# converting_to_smd.net
KiCad netlist of a schematic drawn in EAGLE
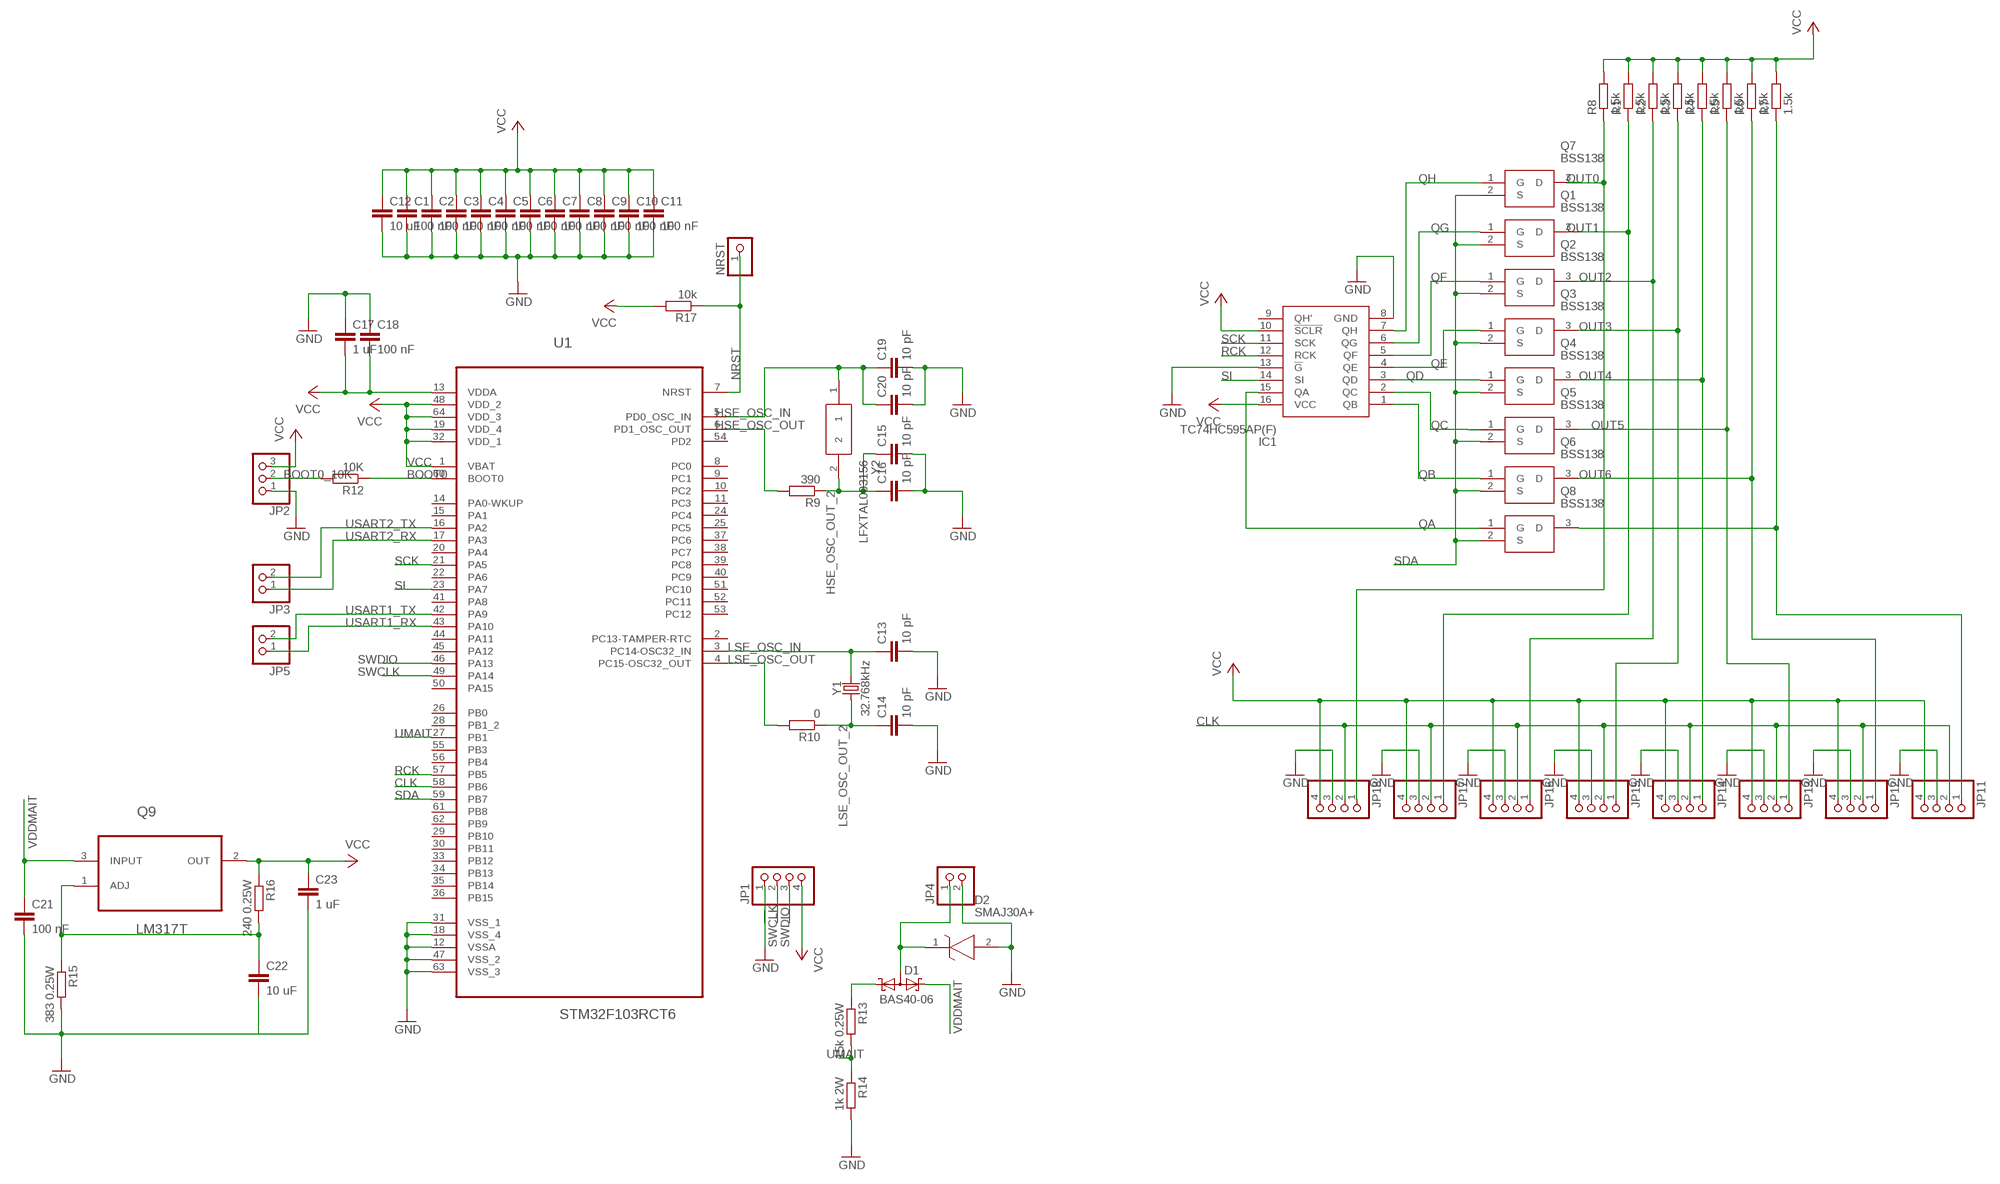
[diagram p0: schematic, sheet 1]

(export (version "E")
  (design (tool "Eeschema 10.0.6"))
  (components
    (comp (ref "C1")
      (value "100 nF")
      (footprint "eagle-import:C0603")
      (libsource (lib "eagle-import") (part "C-EUC0603"))
    )
    (comp (ref "C2")
      (value "100 nF")
      (footprint "eagle-import:C0603")
      (libsource (lib "eagle-import") (part "C-EUC0603"))
    )
    (comp (ref "C3")
      (value "100 nF")
      (footprint "eagle-import:C0603")
      (libsource (lib "eagle-import") (part "C-EUC0603"))
    )
    (comp (ref "C4")
      (value "100 nF")
      (footprint "eagle-import:C0603")
      (libsource (lib "eagle-import") (part "C-EUC0603"))
    )
    (comp (ref "C5")
      (value "100 nF")
      (footprint "eagle-import:C0603")
      (libsource (lib "eagle-import") (part "C-EUC0603"))
    )
    (comp (ref "C6")
      (value "100 nF")
      (footprint "eagle-import:C0603")
      (libsource (lib "eagle-import") (part "C-EUC0603"))
    )
    (comp (ref "C7")
      (value "100 nF")
      (footprint "eagle-import:C0603")
      (libsource (lib "eagle-import") (part "C-EUC0603"))
    )
    (comp (ref "C8")
      (value "100 nF")
      (footprint "eagle-import:C0603")
      (libsource (lib "eagle-import") (part "C-EUC0603"))
    )
    (comp (ref "C9")
      (value "100 nF")
      (footprint "eagle-import:C0603")
      (libsource (lib "eagle-import") (part "C-EUC0603"))
    )
    (comp (ref "C10")
      (value "100 nF")
      (footprint "eagle-import:C0603")
      (libsource (lib "eagle-import") (part "C-EUC0603"))
    )
    (comp (ref "C11")
      (value "100 nF")
      (footprint "eagle-import:C0603")
      (libsource (lib "eagle-import") (part "C-EUC0603"))
    )
    (comp (ref "C12")
      (value "10 uF")
      (footprint "eagle-import:C0603")
      (libsource (lib "eagle-import") (part "resistor_348_C-EUC0603"))
    )
    (comp (ref "C13")
      (value "10 pF")
      (footprint "eagle-import:C0805")
      (libsource (lib "eagle-import") (part "resistor_348_C-EUC0805"))
    )
    (comp (ref "C14")
      (value "10 pF")
      (footprint "eagle-import:C0805")
      (libsource (lib "eagle-import") (part "resistor_348_C-EUC0805"))
    )
    (comp (ref "C15")
      (value "10 pF")
      (footprint "eagle-import:C0805")
      (libsource (lib "eagle-import") (part "resistor_348_C-EUC0805"))
    )
    (comp (ref "C16")
      (value "10 pF")
      (footprint "eagle-import:C0805")
      (libsource (lib "eagle-import") (part "resistor_348_C-EUC0805"))
    )
    (comp (ref "C17")
      (value "1 uF")
      (footprint "eagle-import:C0603")
      (libsource (lib "eagle-import") (part "C-EUC0603"))
    )
    (comp (ref "C18")
      (value "100 nF")
      (footprint "eagle-import:C0603")
      (libsource (lib "eagle-import") (part "C-EUC0603"))
    )
    (comp (ref "C19")
      (value "10 pF")
      (footprint "eagle-import:C0805")
      (libsource (lib "eagle-import") (part "resistor_348_C-EUC0805"))
    )
    (comp (ref "C20")
      (value "10 pF")
      (footprint "eagle-import:C0805")
      (libsource (lib "eagle-import") (part "resistor_348_C-EUC0805"))
    )
    (comp (ref "C21")
      (value "100 nF")
      (footprint "eagle-import:C0603")
      (libsource (lib "eagle-import") (part "C-EUC0603"))
    )
    (comp (ref "C22")
      (value "10 uF")
      (footprint "eagle-import:C0603")
      (libsource (lib "eagle-import") (part "resistor_348_C-EUC0603"))
    )
    (comp (ref "C23")
      (value "1 uF")
      (footprint "eagle-import:C0603")
      (libsource (lib "eagle-import") (part "C-EUC0603"))
    )
    (comp (ref "D1")
      (value "BAS40-06")
      (footprint "eagle-import:SOT23")
      (libsource (lib "eagle-import") (part "BAS40-06"))
    )
    (comp (ref "D2")
      (value "SMAJ30A+")
      (footprint "eagle-import:DIOM5026X262N")
      (libsource (lib "eagle-import") (part "SMAJ30A+"))
    )
    (comp (ref "IC1")
      (value "TC74HC595AP(F)")
      (footprint "eagle-import:DIP762W60P254L1925H445Q16N")
      (fields (field (name "RS_PART_NUMBER") "5400095P"))
      (libsource (lib "eagle-import") (part "TC74HC595AP(F)"))
    )
    (comp (ref "JP1")
      (value "PINHD-1X4")
      (footprint "eagle-import:1X04")
      (libsource (lib "eagle-import") (part "PINHD-1X4"))
    )
    (comp (ref "JP2")
      (value "PINHD-1X3")
      (footprint "eagle-import:1X03")
      (libsource (lib "eagle-import") (part "PINHD-1X3"))
    )
    (comp (ref "JP3")
      (value "PINHD-1X2")
      (footprint "eagle-import:1X02")
      (libsource (lib "eagle-import") (part "PINHD-1X2"))
    )
    (comp (ref "JP4")
      (value "PINHD-1X2")
      (footprint "eagle-import:1X02")
      (libsource (lib "eagle-import") (part "PINHD-1X2"))
    )
    (comp (ref "JP5")
      (value "PINHD-1X2")
      (footprint "eagle-import:1X02")
      (libsource (lib "eagle-import") (part "PINHD-1X2"))
    )
    (comp (ref "JP11")
      (value "PINHD-1X4")
      (footprint "eagle-import:1X04")
      (libsource (lib "eagle-import") (part "PINHD-1X4"))
    )
    (comp (ref "JP12")
      (value "PINHD-1X4")
      (footprint "eagle-import:1X04")
      (libsource (lib "eagle-import") (part "PINHD-1X4"))
    )
    (comp (ref "JP13")
      (value "PINHD-1X4")
      (footprint "eagle-import:1X04")
      (libsource (lib "eagle-import") (part "PINHD-1X4"))
    )
    (comp (ref "JP14")
      (value "PINHD-1X4")
      (footprint "eagle-import:1X04")
      (libsource (lib "eagle-import") (part "PINHD-1X4"))
    )
    (comp (ref "JP15")
      (value "PINHD-1X4")
      (footprint "eagle-import:1X04")
      (libsource (lib "eagle-import") (part "PINHD-1X4"))
    )
    (comp (ref "JP16")
      (value "PINHD-1X4")
      (footprint "eagle-import:1X04")
      (libsource (lib "eagle-import") (part "PINHD-1X4"))
    )
    (comp (ref "JP17")
      (value "PINHD-1X4")
      (footprint "eagle-import:1X04")
      (libsource (lib "eagle-import") (part "PINHD-1X4"))
    )
    (comp (ref "JP18")
      (value "PINHD-1X4")
      (footprint "eagle-import:1X04")
      (libsource (lib "eagle-import") (part "PINHD-1X4"))
    )
    (comp (ref "NRST")
      (value "PINHD-1X1")
      (footprint "eagle-import:1X01")
      (libsource (lib "eagle-import") (part "PINHD-1X1"))
    )
    (comp (ref "Q1")
      (value "BSS138")
      (footprint "eagle-import:SOT95P240X120-3N")
      (fields (field (name "MOUSER_PART_NUMBER") "512-BSS138") (field (name "RS_PART_NUMBER") "1241694"))
      (libsource (lib "eagle-import") (part "BSS138"))
    )
    (comp (ref "Q2")
      (value "BSS138")
      (footprint "eagle-import:SOT95P240X120-3N")
      (fields (field (name "MOUSER_PART_NUMBER") "512-BSS138") (field (name "RS_PART_NUMBER") "1241694"))
      (libsource (lib "eagle-import") (part "BSS138"))
    )
    (comp (ref "Q3")
      (value "BSS138")
      (footprint "eagle-import:SOT95P240X120-3N")
      (fields (field (name "MOUSER_PART_NUMBER") "512-BSS138") (field (name "RS_PART_NUMBER") "1241694"))
      (libsource (lib "eagle-import") (part "BSS138"))
    )
    (comp (ref "Q4")
      (value "BSS138")
      (footprint "eagle-import:SOT95P240X120-3N")
      (fields (field (name "MOUSER_PART_NUMBER") "512-BSS138") (field (name "RS_PART_NUMBER") "1241694"))
      (libsource (lib "eagle-import") (part "BSS138"))
    )
    (comp (ref "Q5")
      (value "BSS138")
      (footprint "eagle-import:SOT95P240X120-3N")
      (fields (field (name "MOUSER_PART_NUMBER") "512-BSS138") (field (name "RS_PART_NUMBER") "1241694"))
      (libsource (lib "eagle-import") (part "BSS138"))
    )
    (comp (ref "Q6")
      (value "BSS138")
      (footprint "eagle-import:SOT95P240X120-3N")
      (fields (field (name "MOUSER_PART_NUMBER") "512-BSS138") (field (name "RS_PART_NUMBER") "1241694"))
      (libsource (lib "eagle-import") (part "BSS138"))
    )
    (comp (ref "Q7")
      (value "BSS138")
      (footprint "eagle-import:SOT95P240X120-3N")
      (fields (field (name "MOUSER_PART_NUMBER") "512-BSS138") (field (name "RS_PART_NUMBER") "1241694"))
      (libsource (lib "eagle-import") (part "BSS138"))
    )
    (comp (ref "Q8")
      (value "BSS138")
      (footprint "eagle-import:SOT95P240X120-3N")
      (fields (field (name "MOUSER_PART_NUMBER") "512-BSS138") (field (name "RS_PART_NUMBER") "1241694"))
      (libsource (lib "eagle-import") (part "BSS138"))
    )
    (comp (ref "Q9")
      (value "LM317T")
      (footprint "eagle-import:TO254P450X1020X2000-3P")
      (fields (field (name "MF") "Texas Instruments"))
      (libsource (lib "eagle-import") (part "LM317T"))
    )
    (comp (ref "R1")
      (value "1.5k")
      (footprint "eagle-import:0207_15")
      (libsource (lib "eagle-import") (part "R-EU_0207/15"))
    )
    (comp (ref "R2")
      (value "1.5k")
      (footprint "eagle-import:0207_15")
      (libsource (lib "eagle-import") (part "R-EU_0207/15"))
    )
    (comp (ref "R3")
      (value "1.5k")
      (footprint "eagle-import:0207_15")
      (libsource (lib "eagle-import") (part "R-EU_0207/15"))
    )
    (comp (ref "R4")
      (value "1.5k")
      (footprint "eagle-import:0207_15")
      (libsource (lib "eagle-import") (part "R-EU_0207/15"))
    )
    (comp (ref "R5")
      (value "1.5k")
      (footprint "eagle-import:0207_15")
      (libsource (lib "eagle-import") (part "R-EU_0207/15"))
    )
    (comp (ref "R6")
      (value "1.5k")
      (footprint "eagle-import:0207_15")
      (libsource (lib "eagle-import") (part "R-EU_0207/15"))
    )
    (comp (ref "R7")
      (value "1.5k")
      (footprint "eagle-import:0207_15")
      (libsource (lib "eagle-import") (part "R-EU_0207/15"))
    )
    (comp (ref "R8")
      (value "1.5k")
      (footprint "eagle-import:0207_15")
      (libsource (lib "eagle-import") (part "R-EU_0207/15"))
    )
    (comp (ref "R9")
      (value "390")
      (footprint "eagle-import:0207_15")
      (libsource (lib "eagle-import") (part "R-EU_0207/15"))
    )
    (comp (ref "R10")
      (value "0")
      (footprint "eagle-import:0207_15")
      (libsource (lib "eagle-import") (part "R-EU_0207/15"))
    )
    (comp (ref "R12")
      (value "10K")
      (footprint "eagle-import:0207_15")
      (libsource (lib "eagle-import") (part "R-EU_0207/15"))
    )
    (comp (ref "R13")
      (value "15k 0.25W")
      (footprint "eagle-import:0207_15")
      (libsource (lib "eagle-import") (part "R-EU_0207/15"))
    )
    (comp (ref "R14")
      (value "1k 2W")
      (footprint "eagle-import:0207_15")
      (libsource (lib "eagle-import") (part "R-EU_0207/15"))
    )
    (comp (ref "R15")
      (value "383 0.25W")
      (footprint "eagle-import:0207_15")
      (libsource (lib "eagle-import") (part "R-EU_0207/15"))
    )
    (comp (ref "R16")
      (value "240 0.25W")
      (footprint "eagle-import:0207_15")
      (libsource (lib "eagle-import") (part "R-EU_0207/15"))
    )
    (comp (ref "R17")
      (value "10k")
      (footprint "eagle-import:0207_15")
      (libsource (lib "eagle-import") (part "R-EU_0207/15"))
    )
    (comp (ref "U1")
      (value "STM32F103RCT6")
      (footprint "eagle-import:QFP50P1200X1200X160-64N")
      (fields (field (name "MF") "STMicroelectronics"))
      (libsource (lib "eagle-import") (part "STM32F103RCT6"))
    )
    (comp (ref "Y1")
      (value "32.768kHz")
      (footprint "eagle-import:CRYSTAL-PTH-2X6-CYL")
      (libsource (lib "eagle-import") (part "CRYSTAL-32.768KHZPTH-2X6"))
    )
    (comp (ref "Y2")
      (value "LFXTAL003156")
      (footprint "eagle-import:IQD-HC-49-4H")
      (fields (field (name "RS_PART_NUMBER") "1533666"))
      (libsource (lib "eagle-import") (part "LFXTAL003156"))
    )
  )
  (nets
    (net (code "1") (name "/BOOT0") (class "Default")
      (node (ref "R12") (pin "1") (pinfunction "1_1") (pintype "passive"))
      (node (ref "U1") (pin "60") (pinfunction "BOOT0_60") (pintype "passive"))
    )
    (net (code "2") (name "/BOOT0_10K") (class "Default")
      (node (ref "JP2") (pin "2") (pinfunction "2_2") (pintype "passive"))
      (node (ref "R12") (pin "2") (pinfunction "2_2") (pintype "passive"))
    )
    (net (code "3") (name "/CLK") (class "Default")
      (node (ref "JP11") (pin "2") (pinfunction "2_2") (pintype "passive"))
      (node (ref "JP12") (pin "2") (pinfunction "2_2") (pintype "passive"))
      (node (ref "JP13") (pin "2") (pinfunction "2_2") (pintype "passive"))
      (node (ref "JP14") (pin "2") (pinfunction "2_2") (pintype "passive"))
      (node (ref "JP15") (pin "2") (pinfunction "2_2") (pintype "passive"))
      (node (ref "JP16") (pin "2") (pinfunction "2_2") (pintype "passive"))
      (node (ref "JP17") (pin "2") (pinfunction "2_2") (pintype "passive"))
      (node (ref "JP18") (pin "2") (pinfunction "2_2") (pintype "passive"))
      (node (ref "U1") (pin "58") (pinfunction "PB6_58") (pintype "bidirectional"))
    )
    (net (code "4") (name "/HSE_OSC_IN") (class "Default")
      (node (ref "C19") (pin "1") (pinfunction "1_1") (pintype "passive"))
      (node (ref "C20") (pin "1") (pinfunction "1_1") (pintype "passive"))
      (node (ref "U1") (pin "5") (pinfunction "PD0_OSC_IN_5") (pintype "input"))
      (node (ref "Y2") (pin "1") (pinfunction "1_1") (pintype "bidirectional"))
    )
    (net (code "5") (name "/HSE_OSC_OUT") (class "Default")
      (node (ref "R9") (pin "2") (pinfunction "2_2") (pintype "passive"))
      (node (ref "U1") (pin "6") (pinfunction "PD1_OSC_OUT_6") (pintype "output"))
    )
    (net (code "6") (name "/HSE_OSC_OUT_2") (class "Default")
      (node (ref "C15") (pin "1") (pinfunction "1_1") (pintype "passive"))
      (node (ref "C16") (pin "1") (pinfunction "1_1") (pintype "passive"))
      (node (ref "R9") (pin "1") (pinfunction "1_1") (pintype "passive"))
      (node (ref "Y2") (pin "2") (pinfunction "2_2") (pintype "bidirectional"))
    )
    (net (code "7") (name "/LSE_OSC_IN") (class "Default")
      (node (ref "C13") (pin "1") (pinfunction "1_1") (pintype "passive"))
      (node (ref "U1") (pin "3") (pinfunction "PC14-OSC32_IN_3") (pintype "input"))
      (node (ref "Y1") (pin "2") (pinfunction "2_2") (pintype "passive"))
    )
    (net (code "8") (name "/LSE_OSC_OUT") (class "Default")
      (node (ref "R10") (pin "2") (pinfunction "2_2") (pintype "passive"))
      (node (ref "U1") (pin "4") (pinfunction "PC15-OSC32_OUT_4") (pintype "output"))
    )
    (net (code "9") (name "/LSE_OSC_OUT_2") (class "Default")
      (node (ref "C14") (pin "1") (pinfunction "1_1") (pintype "passive"))
      (node (ref "R10") (pin "1") (pinfunction "1_1") (pintype "passive"))
      (node (ref "Y1") (pin "1") (pinfunction "1_1") (pintype "passive"))
    )
    (net (code "10") (name "/NRST") (class "Default")
      (node (ref "NRST") (pin "1") (pinfunction "1_1") (pintype "passive"))
      (node (ref "R17") (pin "1") (pinfunction "1_1") (pintype "passive"))
      (node (ref "U1") (pin "7") (pinfunction "NRST_7") (pintype "output"))
    )
    (net (code "11") (name "/OUT0") (class "Default")
      (node (ref "JP18") (pin "1") (pinfunction "1_1") (pintype "passive"))
      (node (ref "Q7") (pin "3") (pinfunction "D_3") (pintype "bidirectional"))
      (node (ref "R8") (pin "1") (pinfunction "1_1") (pintype "passive"))
    )
    (net (code "12") (name "/OUT1") (class "Default")
      (node (ref "JP17") (pin "1") (pinfunction "1_1") (pintype "passive"))
      (node (ref "Q1") (pin "3") (pinfunction "D_3") (pintype "bidirectional"))
      (node (ref "R1") (pin "1") (pinfunction "1_1") (pintype "passive"))
    )
    (net (code "13") (name "/OUT2") (class "Default")
      (node (ref "JP16") (pin "1") (pinfunction "1_1") (pintype "passive"))
      (node (ref "Q2") (pin "3") (pinfunction "D_3") (pintype "bidirectional"))
      (node (ref "R2") (pin "1") (pinfunction "1_1") (pintype "passive"))
    )
    (net (code "14") (name "/OUT3") (class "Default")
      (node (ref "JP15") (pin "1") (pinfunction "1_1") (pintype "passive"))
      (node (ref "Q3") (pin "3") (pinfunction "D_3") (pintype "bidirectional"))
      (node (ref "R3") (pin "1") (pinfunction "1_1") (pintype "passive"))
    )
    (net (code "15") (name "/OUT4") (class "Default")
      (node (ref "JP14") (pin "1") (pinfunction "1_1") (pintype "passive"))
      (node (ref "Q4") (pin "3") (pinfunction "D_3") (pintype "bidirectional"))
      (node (ref "R4") (pin "1") (pinfunction "1_1") (pintype "passive"))
    )
    (net (code "16") (name "/OUT5") (class "Default")
      (node (ref "JP13") (pin "1") (pinfunction "1_1") (pintype "passive"))
      (node (ref "Q5") (pin "3") (pinfunction "D_3") (pintype "bidirectional"))
      (node (ref "R5") (pin "1") (pinfunction "1_1") (pintype "passive"))
    )
    (net (code "17") (name "/OUT6") (class "Default")
      (node (ref "JP12") (pin "1") (pinfunction "1_1") (pintype "passive"))
      (node (ref "Q6") (pin "3") (pinfunction "D_3") (pintype "bidirectional"))
      (node (ref "R6") (pin "1") (pinfunction "1_1") (pintype "passive"))
    )
    (net (code "18") (name "/QA") (class "Default")
      (node (ref "IC1") (pin "15") (pinfunction "QA_15") (pintype "bidirectional"))
      (node (ref "Q8") (pin "1") (pinfunction "G_1") (pintype "bidirectional"))
    )
    (net (code "19") (name "/QB") (class "Default")
      (node (ref "IC1") (pin "1") (pinfunction "QB_1") (pintype "bidirectional"))
      (node (ref "Q6") (pin "1") (pinfunction "G_1") (pintype "bidirectional"))
    )
    (net (code "20") (name "/QC") (class "Default")
      (node (ref "IC1") (pin "2") (pinfunction "QC_2") (pintype "bidirectional"))
      (node (ref "Q5") (pin "1") (pinfunction "G_1") (pintype "bidirectional"))
    )
    (net (code "21") (name "/QD") (class "Default")
      (node (ref "IC1") (pin "3") (pinfunction "QD_3") (pintype "bidirectional"))
      (node (ref "Q4") (pin "1") (pinfunction "G_1") (pintype "bidirectional"))
    )
    (net (code "22") (name "/QE") (class "Default")
      (node (ref "IC1") (pin "4") (pinfunction "QE_4") (pintype "bidirectional"))
      (node (ref "Q3") (pin "1") (pinfunction "G_1") (pintype "bidirectional"))
    )
    (net (code "23") (name "/QF") (class "Default")
      (node (ref "IC1") (pin "5") (pinfunction "QF_5") (pintype "bidirectional"))
      (node (ref "Q2") (pin "1") (pinfunction "G_1") (pintype "bidirectional"))
    )
    (net (code "24") (name "/QG") (class "Default")
      (node (ref "IC1") (pin "6") (pinfunction "QG_6") (pintype "bidirectional"))
      (node (ref "Q1") (pin "1") (pinfunction "G_1") (pintype "bidirectional"))
    )
    (net (code "25") (name "/QH") (class "Default")
      (node (ref "IC1") (pin "7") (pinfunction "QH_7") (pintype "bidirectional"))
      (node (ref "Q7") (pin "1") (pinfunction "G_1") (pintype "bidirectional"))
    )
    (net (code "26") (name "/RCK") (class "Default")
      (node (ref "IC1") (pin "12") (pinfunction "RCK_12") (pintype "bidirectional"))
      (node (ref "U1") (pin "57") (pinfunction "PB5_57") (pintype "bidirectional"))
    )
    (net (code "27") (name "/SCK") (class "Default")
      (node (ref "IC1") (pin "11") (pinfunction "SCK_11") (pintype "bidirectional"))
      (node (ref "U1") (pin "21") (pinfunction "PA5_21") (pintype "bidirectional"))
    )
    (net (code "28") (name "/SDA") (class "Default")
      (node (ref "Q1") (pin "2") (pinfunction "S_2") (pintype "bidirectional"))
      (node (ref "Q2") (pin "2") (pinfunction "S_2") (pintype "bidirectional"))
      (node (ref "Q3") (pin "2") (pinfunction "S_2") (pintype "bidirectional"))
      (node (ref "Q4") (pin "2") (pinfunction "S_2") (pintype "bidirectional"))
      (node (ref "Q5") (pin "2") (pinfunction "S_2") (pintype "bidirectional"))
      (node (ref "Q6") (pin "2") (pinfunction "S_2") (pintype "bidirectional"))
      (node (ref "Q7") (pin "2") (pinfunction "S_2") (pintype "bidirectional"))
      (node (ref "Q8") (pin "2") (pinfunction "S_2") (pintype "bidirectional"))
      (node (ref "U1") (pin "59") (pinfunction "PB7_59") (pintype "power_in"))
    )
    (net (code "29") (name "/SI") (class "Default")
      (node (ref "IC1") (pin "14") (pinfunction "SI_14") (pintype "bidirectional"))
      (node (ref "U1") (pin "23") (pinfunction "PA7_23") (pintype "power_in"))
    )
    (net (code "30") (name "/SWCLK") (class "Default")
      (node (ref "JP1") (pin "2") (pinfunction "2_2") (pintype "passive"))
      (node (ref "U1") (pin "49") (pinfunction "PA14_49") (pintype "bidirectional"))
    )
    (net (code "31") (name "/SWDIO") (class "Default")
      (node (ref "JP1") (pin "3") (pinfunction "3_3") (pintype "passive"))
      (node (ref "U1") (pin "46") (pinfunction "PA13_46") (pintype "bidirectional"))
    )
    (net (code "32") (name "/UMAIT") (class "Default")
      (node (ref "R13") (pin "2") (pinfunction "2_2") (pintype "passive"))
      (node (ref "R14") (pin "1") (pinfunction "1_1") (pintype "passive"))
      (node (ref "U1") (pin "27") (pinfunction "PB1_27") (pintype "bidirectional"))
    )
    (net (code "33") (name "/USART1_RX") (class "Default")
      (node (ref "JP5") (pin "1") (pinfunction "1_1") (pintype "passive"))
      (node (ref "U1") (pin "43") (pinfunction "PA10_43") (pintype "bidirectional"))
    )
    (net (code "34") (name "/USART1_TX") (class "Default")
      (node (ref "JP5") (pin "2") (pinfunction "2_2") (pintype "passive"))
      (node (ref "U1") (pin "42") (pinfunction "PA9_42") (pintype "bidirectional"))
    )
    (net (code "35") (name "/USART2_RX") (class "Default")
      (node (ref "JP3") (pin "1") (pinfunction "1_1") (pintype "passive"))
      (node (ref "U1") (pin "17") (pinfunction "PA3_17") (pintype "bidirectional"))
    )
    (net (code "36") (name "/USART2_TX") (class "Default")
      (node (ref "JP3") (pin "2") (pinfunction "2_2") (pintype "passive"))
      (node (ref "U1") (pin "16") (pinfunction "PA2_16") (pintype "bidirectional"))
    )
    (net (code "37") (name "/VDDMAIT") (class "Default")
      (node (ref "C21") (pin "1") (pinfunction "1_1") (pintype "passive"))
      (node (ref "D1") (pin "2") (pinfunction "K2_2") (pintype "passive"))
      (node (ref "Q9") (pin "3") (pinfunction "INPUT_3") (pintype "input"))
    )
    (net (code "38") (name "GND") (class "Default")
      (node (ref "C1") (pin "2") (pinfunction "2_2") (pintype "passive"))
      (node (ref "C10") (pin "2") (pinfunction "2_2") (pintype "passive"))
      (node (ref "C11") (pin "2") (pinfunction "2_2") (pintype "passive"))
      (node (ref "C12") (pin "2") (pinfunction "2_2") (pintype "passive"))
      (node (ref "C13") (pin "2") (pinfunction "2_2") (pintype "passive"))
      (node (ref "C14") (pin "2") (pinfunction "2_2") (pintype "passive"))
      (node (ref "C15") (pin "2") (pinfunction "2_2") (pintype "passive"))
      (node (ref "C16") (pin "2") (pinfunction "2_2") (pintype "passive"))
      (node (ref "C17") (pin "1") (pinfunction "1_1") (pintype "passive"))
      (node (ref "C18") (pin "1") (pinfunction "1_1") (pintype "passive"))
      (node (ref "C19") (pin "2") (pinfunction "2_2") (pintype "passive"))
      (node (ref "C2") (pin "2") (pinfunction "2_2") (pintype "passive"))
      (node (ref "C20") (pin "2") (pinfunction "2_2") (pintype "passive"))
      (node (ref "C21") (pin "2") (pinfunction "2_2") (pintype "passive"))
      (node (ref "C22") (pin "2") (pinfunction "2_2") (pintype "passive"))
      (node (ref "C23") (pin "2") (pinfunction "2_2") (pintype "passive"))
      (node (ref "C3") (pin "2") (pinfunction "2_2") (pintype "passive"))
      (node (ref "C4") (pin "2") (pinfunction "2_2") (pintype "passive"))
      (node (ref "C5") (pin "2") (pinfunction "2_2") (pintype "passive"))
      (node (ref "C6") (pin "2") (pinfunction "2_2") (pintype "passive"))
      (node (ref "C7") (pin "2") (pinfunction "2_2") (pintype "passive"))
      (node (ref "C8") (pin "2") (pinfunction "2_2") (pintype "passive"))
      (node (ref "C9") (pin "2") (pinfunction "2_2") (pintype "passive"))
      (node (ref "D2") (pin "2") (pinfunction "A_2") (pintype "bidirectional"))
      (node (ref "IC1") (pin "13") (pinfunction "~{G}_13") (pintype "bidirectional"))
      (node (ref "IC1") (pin "8") (pinfunction "GND_8") (pintype "bidirectional"))
      (node (ref "JP1") (pin "1") (pinfunction "1_1") (pintype "passive"))
      (node (ref "JP11") (pin "3") (pinfunction "3_3") (pintype "passive"))
      (node (ref "JP12") (pin "3") (pinfunction "3_3") (pintype "passive"))
      (node (ref "JP13") (pin "3") (pinfunction "3_3") (pintype "passive"))
      (node (ref "JP14") (pin "3") (pinfunction "3_3") (pintype "passive"))
      (node (ref "JP15") (pin "3") (pinfunction "3_3") (pintype "passive"))
      (node (ref "JP16") (pin "3") (pinfunction "3_3") (pintype "passive"))
      (node (ref "JP17") (pin "3") (pinfunction "3_3") (pintype "passive"))
      (node (ref "JP18") (pin "3") (pinfunction "3_3") (pintype "passive"))
      (node (ref "JP2") (pin "1") (pinfunction "1_1") (pintype "passive"))
      (node (ref "JP4") (pin "2") (pinfunction "2_2") (pintype "passive"))
      (node (ref "R14") (pin "2") (pinfunction "2_2") (pintype "passive"))
      (node (ref "R15") (pin "2") (pinfunction "2_2") (pintype "passive"))
      (node (ref "U1") (pin "12") (pinfunction "VSSA_12") (pintype "passive"))
      (node (ref "U1") (pin "18") (pinfunction "VSS_4_18") (pintype "passive"))
      (node (ref "U1") (pin "31") (pinfunction "VSS_1_31") (pintype "passive"))
      (node (ref "U1") (pin "47") (pinfunction "VSS_2_47") (pintype "passive"))
      (node (ref "U1") (pin "63") (pinfunction "VSS_3_63") (pintype "passive"))
    )
    (net (code "39") (name "Net-(D1-AA)") (class "Default")
      (node (ref "D1") (pin "3") (pinfunction "AA_3") (pintype "passive"))
      (node (ref "D2") (pin "1") (pinfunction "K_1") (pintype "bidirectional"))
      (node (ref "JP4") (pin "1") (pinfunction "1_1") (pintype "passive"))
    )
    (net (code "40") (name "Net-(D1-K1)") (class "Default")
      (node (ref "D1") (pin "1") (pinfunction "K1_1") (pintype "passive"))
      (node (ref "R13") (pin "1") (pinfunction "1_1") (pintype "passive"))
    )
    (net (code "41") (name "Net-(Q8-D)") (class "Default")
      (node (ref "JP11") (pin "1") (pinfunction "1_1") (pintype "passive"))
      (node (ref "Q8") (pin "3") (pinfunction "D_3") (pintype "bidirectional"))
      (node (ref "R7") (pin "1") (pinfunction "1_1") (pintype "passive"))
    )
    (net (code "42") (name "Net-(Q9-ADJ)") (class "Default")
      (node (ref "C22") (pin "1") (pinfunction "1_1") (pintype "passive"))
      (node (ref "Q9") (pin "1") (pinfunction "ADJ_1") (pintype "input"))
      (node (ref "R15") (pin "1") (pinfunction "1_1") (pintype "passive"))
      (node (ref "R16") (pin "2") (pinfunction "2_2") (pintype "passive"))
    )
    (net (code "43") (name "VCC") (class "Default")
      (node (ref "C1") (pin "1") (pinfunction "1_1") (pintype "passive"))
      (node (ref "C10") (pin "1") (pinfunction "1_1") (pintype "passive"))
      (node (ref "C11") (pin "1") (pinfunction "1_1") (pintype "passive"))
      (node (ref "C12") (pin "1") (pinfunction "1_1") (pintype "passive"))
      (node (ref "C17") (pin "2") (pinfunction "2_2") (pintype "passive"))
      (node (ref "C18") (pin "2") (pinfunction "2_2") (pintype "passive"))
      (node (ref "C2") (pin "1") (pinfunction "1_1") (pintype "passive"))
      (node (ref "C23") (pin "1") (pinfunction "1_1") (pintype "passive"))
      (node (ref "C3") (pin "1") (pinfunction "1_1") (pintype "passive"))
      (node (ref "C4") (pin "1") (pinfunction "1_1") (pintype "passive"))
      (node (ref "C5") (pin "1") (pinfunction "1_1") (pintype "passive"))
      (node (ref "C6") (pin "1") (pinfunction "1_1") (pintype "passive"))
      (node (ref "C7") (pin "1") (pinfunction "1_1") (pintype "passive"))
      (node (ref "C8") (pin "1") (pinfunction "1_1") (pintype "passive"))
      (node (ref "C9") (pin "1") (pinfunction "1_1") (pintype "passive"))
      (node (ref "IC1") (pin "10") (pinfunction "~{SCLR}_10") (pintype "bidirectional"))
      (node (ref "IC1") (pin "16") (pinfunction "VCC_16") (pintype "bidirectional"))
      (node (ref "JP1") (pin "4") (pinfunction "4_4") (pintype "passive"))
      (node (ref "JP11") (pin "4") (pinfunction "4_4") (pintype "passive"))
      (node (ref "JP12") (pin "4") (pinfunction "4_4") (pintype "passive"))
      (node (ref "JP13") (pin "4") (pinfunction "4_4") (pintype "passive"))
      (node (ref "JP14") (pin "4") (pinfunction "4_4") (pintype "passive"))
      (node (ref "JP15") (pin "4") (pinfunction "4_4") (pintype "passive"))
      (node (ref "JP16") (pin "4") (pinfunction "4_4") (pintype "passive"))
      (node (ref "JP17") (pin "4") (pinfunction "4_4") (pintype "passive"))
      (node (ref "JP18") (pin "4") (pinfunction "4_4") (pintype "passive"))
      (node (ref "JP2") (pin "3") (pinfunction "3_3") (pintype "passive"))
      (node (ref "Q9") (pin "2") (pinfunction "OUT_2") (pintype "output"))
      (node (ref "R1") (pin "2") (pinfunction "2_2") (pintype "passive"))
      (node (ref "R16") (pin "1") (pinfunction "1_1") (pintype "passive"))
      (node (ref "R17") (pin "2") (pinfunction "2_2") (pintype "passive"))
      (node (ref "R2") (pin "2") (pinfunction "2_2") (pintype "passive"))
      (node (ref "R3") (pin "2") (pinfunction "2_2") (pintype "passive"))
      (node (ref "R4") (pin "2") (pinfunction "2_2") (pintype "passive"))
      (node (ref "R5") (pin "2") (pinfunction "2_2") (pintype "passive"))
      (node (ref "R6") (pin "2") (pinfunction "2_2") (pintype "passive"))
      (node (ref "R7") (pin "2") (pinfunction "2_2") (pintype "passive"))
      (node (ref "R8") (pin "2") (pinfunction "2_2") (pintype "passive"))
      (node (ref "U1") (pin "1") (pinfunction "VBAT_1") (pintype "input"))
      (node (ref "U1") (pin "13") (pinfunction "VDDA_13") (pintype "power_in"))
      (node (ref "U1") (pin "19") (pinfunction "VDD_4_19") (pintype "power_in"))
      (node (ref "U1") (pin "32") (pinfunction "VDD_1_32") (pintype "power_in"))
      (node (ref "U1") (pin "48") (pinfunction "VDD_2_48") (pintype "power_in"))
      (node (ref "U1") (pin "64") (pinfunction "VDD_3_64") (pintype "power_in"))
    )
    (net (code "44") (name "unconnected-(IC1-QH'-Pad9)") (class "Default")
      (node (ref "IC1") (pin "9") (pinfunction "QH'_9") (pintype "bidirectional"))
    )
    (net (code "45") (name "unconnected-(U1-PA0-WKUP-Pad14)") (class "Default")
      (node (ref "U1") (pin "14") (pinfunction "PA0-WKUP_14") (pintype "bidirectional"))
    )
    (net (code "46") (name "unconnected-(U1-PA1-Pad15)") (class "Default")
      (node (ref "U1") (pin "15") (pinfunction "PA1_15") (pintype "bidirectional"))
    )
    (net (code "47") (name "unconnected-(U1-PA4-Pad20)") (class "Default")
      (node (ref "U1") (pin "20") (pinfunction "PA4_20") (pintype "bidirectional"))
    )
    (net (code "48") (name "unconnected-(U1-PA6-Pad22)") (class "Default")
      (node (ref "U1") (pin "22") (pinfunction "PA6_22") (pintype "bidirectional"))
    )
    (net (code "49") (name "unconnected-(U1-PA8-Pad41)") (class "Default")
      (node (ref "U1") (pin "41") (pinfunction "PA8_41") (pintype "bidirectional"))
    )
    (net (code "50") (name "unconnected-(U1-PA11-Pad44)") (class "Default")
      (node (ref "U1") (pin "44") (pinfunction "PA11_44") (pintype "bidirectional"))
    )
    (net (code "51") (name "unconnected-(U1-PA12-Pad45)") (class "Default")
      (node (ref "U1") (pin "45") (pinfunction "PA12_45") (pintype "bidirectional"))
    )
    (net (code "52") (name "unconnected-(U1-PA15-Pad50)") (class "Default")
      (node (ref "U1") (pin "50") (pinfunction "PA15_50") (pintype "bidirectional"))
    )
    (net (code "53") (name "unconnected-(U1-PB0-Pad26)") (class "Default")
      (node (ref "U1") (pin "26") (pinfunction "PB0_26") (pintype "bidirectional"))
    )
    (net (code "54") (name "unconnected-(U1-PB1_2-Pad28)") (class "Default")
      (node (ref "U1") (pin "28") (pinfunction "PB1_2_28") (pintype "bidirectional"))
    )
    (net (code "55") (name "unconnected-(U1-PB3-Pad55)") (class "Default")
      (node (ref "U1") (pin "55") (pinfunction "PB3_55") (pintype "bidirectional"))
    )
    (net (code "56") (name "unconnected-(U1-PB4-Pad56)") (class "Default")
      (node (ref "U1") (pin "56") (pinfunction "PB4_56") (pintype "bidirectional"))
    )
    (net (code "57") (name "unconnected-(U1-PB8-Pad61)") (class "Default")
      (node (ref "U1") (pin "61") (pinfunction "PB8_61") (pintype "bidirectional"))
    )
    (net (code "58") (name "unconnected-(U1-PB9-Pad62)") (class "Default")
      (node (ref "U1") (pin "62") (pinfunction "PB9_62") (pintype "bidirectional"))
    )
    (net (code "59") (name "unconnected-(U1-PB10-Pad29)") (class "Default")
      (node (ref "U1") (pin "29") (pinfunction "PB10_29") (pintype "bidirectional"))
    )
    (net (code "60") (name "unconnected-(U1-PB11-Pad30)") (class "Default")
      (node (ref "U1") (pin "30") (pinfunction "PB11_30") (pintype "bidirectional"))
    )
    (net (code "61") (name "unconnected-(U1-PB12-Pad33)") (class "Default")
      (node (ref "U1") (pin "33") (pinfunction "PB12_33") (pintype "bidirectional"))
    )
    (net (code "62") (name "unconnected-(U1-PB13-Pad34)") (class "Default")
      (node (ref "U1") (pin "34") (pinfunction "PB13_34") (pintype "bidirectional"))
    )
    (net (code "63") (name "unconnected-(U1-PB14-Pad35)") (class "Default")
      (node (ref "U1") (pin "35") (pinfunction "PB14_35") (pintype "bidirectional"))
    )
    (net (code "64") (name "unconnected-(U1-PB15-Pad36)") (class "Default")
      (node (ref "U1") (pin "36") (pinfunction "PB15_36") (pintype "bidirectional"))
    )
    (net (code "65") (name "unconnected-(U1-PC0-Pad8)") (class "Default")
      (node (ref "U1") (pin "8") (pinfunction "PC0_8") (pintype "bidirectional"))
    )
    (net (code "66") (name "unconnected-(U1-PC1-Pad9)") (class "Default")
      (node (ref "U1") (pin "9") (pinfunction "PC1_9") (pintype "bidirectional"))
    )
    (net (code "67") (name "unconnected-(U1-PC2-Pad10)") (class "Default")
      (node (ref "U1") (pin "10") (pinfunction "PC2_10") (pintype "bidirectional"))
    )
    (net (code "68") (name "unconnected-(U1-PC3-Pad11)") (class "Default")
      (node (ref "U1") (pin "11") (pinfunction "PC3_11") (pintype "bidirectional"))
    )
    (net (code "69") (name "unconnected-(U1-PC4-Pad24)") (class "Default")
      (node (ref "U1") (pin "24") (pinfunction "PC4_24") (pintype "passive"))
    )
    (net (code "70") (name "unconnected-(U1-PC5-Pad25)") (class "Default")
      (node (ref "U1") (pin "25") (pinfunction "PC5_25") (pintype "bidirectional"))
    )
    (net (code "71") (name "unconnected-(U1-PC6-Pad37)") (class "Default")
      (node (ref "U1") (pin "37") (pinfunction "PC6_37") (pintype "bidirectional"))
    )
    (net (code "72") (name "unconnected-(U1-PC7-Pad38)") (class "Default")
      (node (ref "U1") (pin "38") (pinfunction "PC7_38") (pintype "bidirectional"))
    )
    (net (code "73") (name "unconnected-(U1-PC8-Pad39)") (class "Default")
      (node (ref "U1") (pin "39") (pinfunction "PC8_39") (pintype "bidirectional"))
    )
    (net (code "74") (name "unconnected-(U1-PC9-Pad40)") (class "Default")
      (node (ref "U1") (pin "40") (pinfunction "PC9_40") (pintype "bidirectional"))
    )
    (net (code "75") (name "unconnected-(U1-PC10-Pad51)") (class "Default")
      (node (ref "U1") (pin "51") (pinfunction "PC10_51") (pintype "bidirectional"))
    )
    (net (code "76") (name "unconnected-(U1-PC11-Pad52)") (class "Default")
      (node (ref "U1") (pin "52") (pinfunction "PC11_52") (pintype "bidirectional"))
    )
    (net (code "77") (name "unconnected-(U1-PC12-Pad53)") (class "Default")
      (node (ref "U1") (pin "53") (pinfunction "PC12_53") (pintype "bidirectional"))
    )
    (net (code "78") (name "unconnected-(U1-PC13-TAMPER-RTC-Pad2)") (class "Default")
      (node (ref "U1") (pin "2") (pinfunction "PC13-TAMPER-RTC_2") (pintype "input"))
    )
    (net (code "79") (name "unconnected-(U1-PD2-Pad54)") (class "Default")
      (node (ref "U1") (pin "54") (pinfunction "PD2_54") (pintype "bidirectional"))
    )
  )
)
